# Quimera_Power-Input.net
KiCad netlist of a schematic drawn in EAGLE
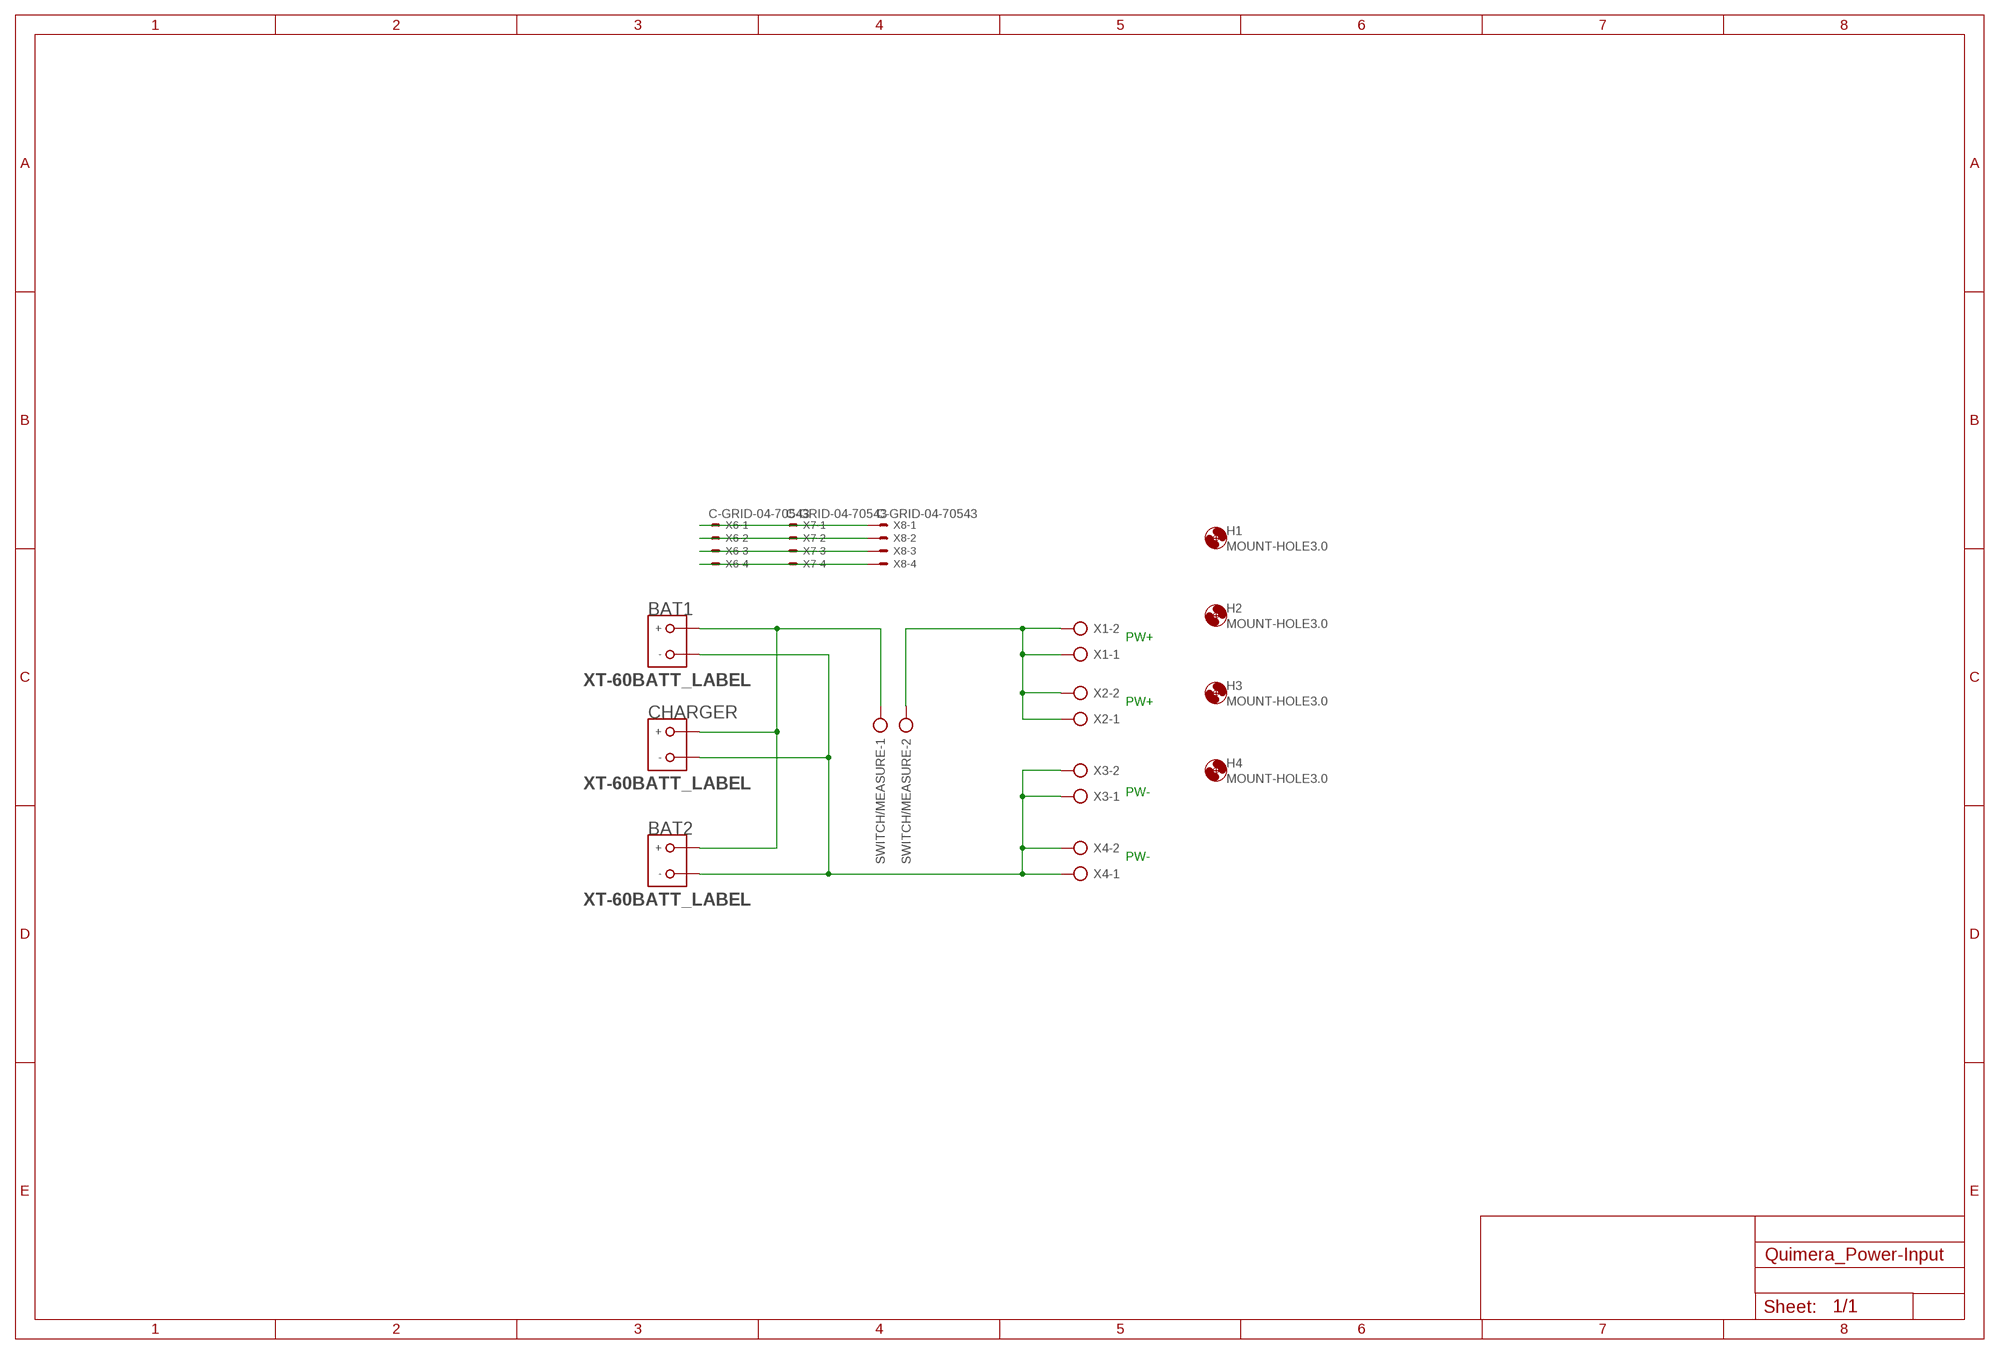
[diagram p0: schematic, sheet 1]

(export (version "E")
  (design (tool "Eeschema 10.0.6"))
  (components
    (comp (ref "BAT1")
      (value "XT-60BATT_LABEL")
      (footprint "eagle-import:XT-60")
      (libsource (lib "eagle-import") (part "XT-60BATT_LABEL"))
    )
    (comp (ref "BAT2")
      (value "XT-60BATT_LABEL")
      (footprint "eagle-import:XT-60")
      (libsource (lib "eagle-import") (part "XT-60BATT_LABEL"))
    )
    (comp (ref "CHARGER")
      (value "XT-60BATT_LABEL")
      (footprint "eagle-import:XT-60")
      (libsource (lib "eagle-import") (part "XT-60BATT_LABEL"))
    )
    (comp (ref "H1")
      (value "MOUNT-HOLE3.0")
      (footprint "eagle-import:3,0")
      (libsource (lib "eagle-import") (part "MOUNT-HOLE3.0"))
    )
    (comp (ref "H2")
      (value "MOUNT-HOLE3.0")
      (footprint "eagle-import:3,0")
      (libsource (lib "eagle-import") (part "MOUNT-HOLE3.0"))
    )
    (comp (ref "H3")
      (value "MOUNT-HOLE3.0")
      (footprint "eagle-import:3,0")
      (libsource (lib "eagle-import") (part "MOUNT-HOLE3.0"))
    )
    (comp (ref "H4")
      (value "MOUNT-HOLE3.0")
      (footprint "eagle-import:3,0")
      (libsource (lib "eagle-import") (part "MOUNT-HOLE3.0"))
    )
    (comp (ref "SWITCH/MEASURE")
      (value "AK500/2")
      (footprint "eagle-import:AK500_2")
      (libsource (lib "eagle-import") (part "AK500/2"))
    )
    (comp (ref "X1")
      (value "AK500/2")
      (footprint "eagle-import:AK500_2")
      (libsource (lib "eagle-import") (part "AK500/2"))
    )
    (comp (ref "X2")
      (value "AK500/2")
      (footprint "eagle-import:AK500_2")
      (libsource (lib "eagle-import") (part "AK500/2"))
    )
    (comp (ref "X3")
      (value "AK500/2")
      (footprint "eagle-import:AK500_2")
      (libsource (lib "eagle-import") (part "AK500/2"))
    )
    (comp (ref "X4")
      (value "AK500/2")
      (footprint "eagle-import:AK500_2")
      (libsource (lib "eagle-import") (part "AK500/2"))
    )
    (comp (ref "X6")
      (value "C-GRID-04-70543")
      (footprint "eagle-import:70543-04")
      (libsource (lib "eagle-import") (part "C-GRID-04-70543"))
    )
    (comp (ref "X7")
      (value "C-GRID-04-70543")
      (footprint "eagle-import:70543-04")
      (libsource (lib "eagle-import") (part "C-GRID-04-70543"))
    )
    (comp (ref "X8")
      (value "C-GRID-04-70543")
      (footprint "eagle-import:70543-04")
      (libsource (lib "eagle-import") (part "C-GRID-04-70543"))
    )
  )
  (nets
    (net (code "1") (name "Net-(BAT1-+)") (class "Default")
      (node (ref "BAT1") (pin "BATT") (pinfunction "+_BATT") (pintype "passive"))
      (node (ref "BAT2") (pin "BATT") (pinfunction "+_BATT") (pintype "passive"))
      (node (ref "CHARGER") (pin "BATT") (pinfunction "+_BATT") (pintype "passive"))
      (node (ref "SWITCH/MEASURE") (pin "1") (pinfunction "KL_1") (pintype "passive"))
    )
    (net (code "2") (name "Net-(BAT1--)") (class "Default")
      (node (ref "BAT1") (pin "GND") (pinfunction "-_GND") (pintype "passive"))
      (node (ref "BAT2") (pin "GND") (pinfunction "-_GND") (pintype "passive"))
      (node (ref "CHARGER") (pin "GND") (pinfunction "-_GND") (pintype "passive"))
      (node (ref "X3") (pin "1") (pinfunction "KL_1") (pintype "passive"))
      (node (ref "X3") (pin "2") (pinfunction "KL_2") (pintype "passive"))
      (node (ref "X4") (pin "1") (pinfunction "KL_1") (pintype "passive"))
      (node (ref "X4") (pin "2") (pinfunction "KL_2") (pintype "passive"))
    )
    (net (code "3") (name "Net-(SWITCH/MEASUREB-KL)") (class "Default")
      (node (ref "SWITCH/MEASURE") (pin "2") (pinfunction "KL_2") (pintype "passive"))
      (node (ref "X1") (pin "1") (pinfunction "KL_1") (pintype "passive"))
      (node (ref "X1") (pin "2") (pinfunction "KL_2") (pintype "passive"))
      (node (ref "X2") (pin "1") (pinfunction "KL_1") (pintype "passive"))
      (node (ref "X2") (pin "2") (pinfunction "KL_2") (pintype "passive"))
    )
    (net (code "4") (name "Net-(X6A-S)") (class "Default")
      (node (ref "X6") (pin "1") (pinfunction "S_1") (pintype "passive"))
      (node (ref "X7") (pin "1") (pinfunction "S_1") (pintype "passive"))
      (node (ref "X8") (pin "1") (pinfunction "S_1") (pintype "passive"))
    )
    (net (code "5") (name "Net-(X6B-S)") (class "Default")
      (node (ref "X6") (pin "2") (pinfunction "S_2") (pintype "passive"))
      (node (ref "X7") (pin "2") (pinfunction "S_2") (pintype "passive"))
      (node (ref "X8") (pin "2") (pinfunction "S_2") (pintype "passive"))
    )
    (net (code "6") (name "Net-(X6C-S)") (class "Default")
      (node (ref "X6") (pin "3") (pinfunction "S_3") (pintype "passive"))
      (node (ref "X7") (pin "3") (pinfunction "S_3") (pintype "passive"))
      (node (ref "X8") (pin "3") (pinfunction "S_3") (pintype "passive"))
    )
    (net (code "7") (name "Net-(X6D-S)") (class "Default")
      (node (ref "X6") (pin "4") (pinfunction "S_4") (pintype "passive"))
      (node (ref "X7") (pin "4") (pinfunction "S_4") (pintype "passive"))
      (node (ref "X8") (pin "4") (pinfunction "S_4") (pintype "passive"))
    )
  )
)
